# robotWagen_arrduino.net
KiCad netlist of a schematic drawn in EAGLE
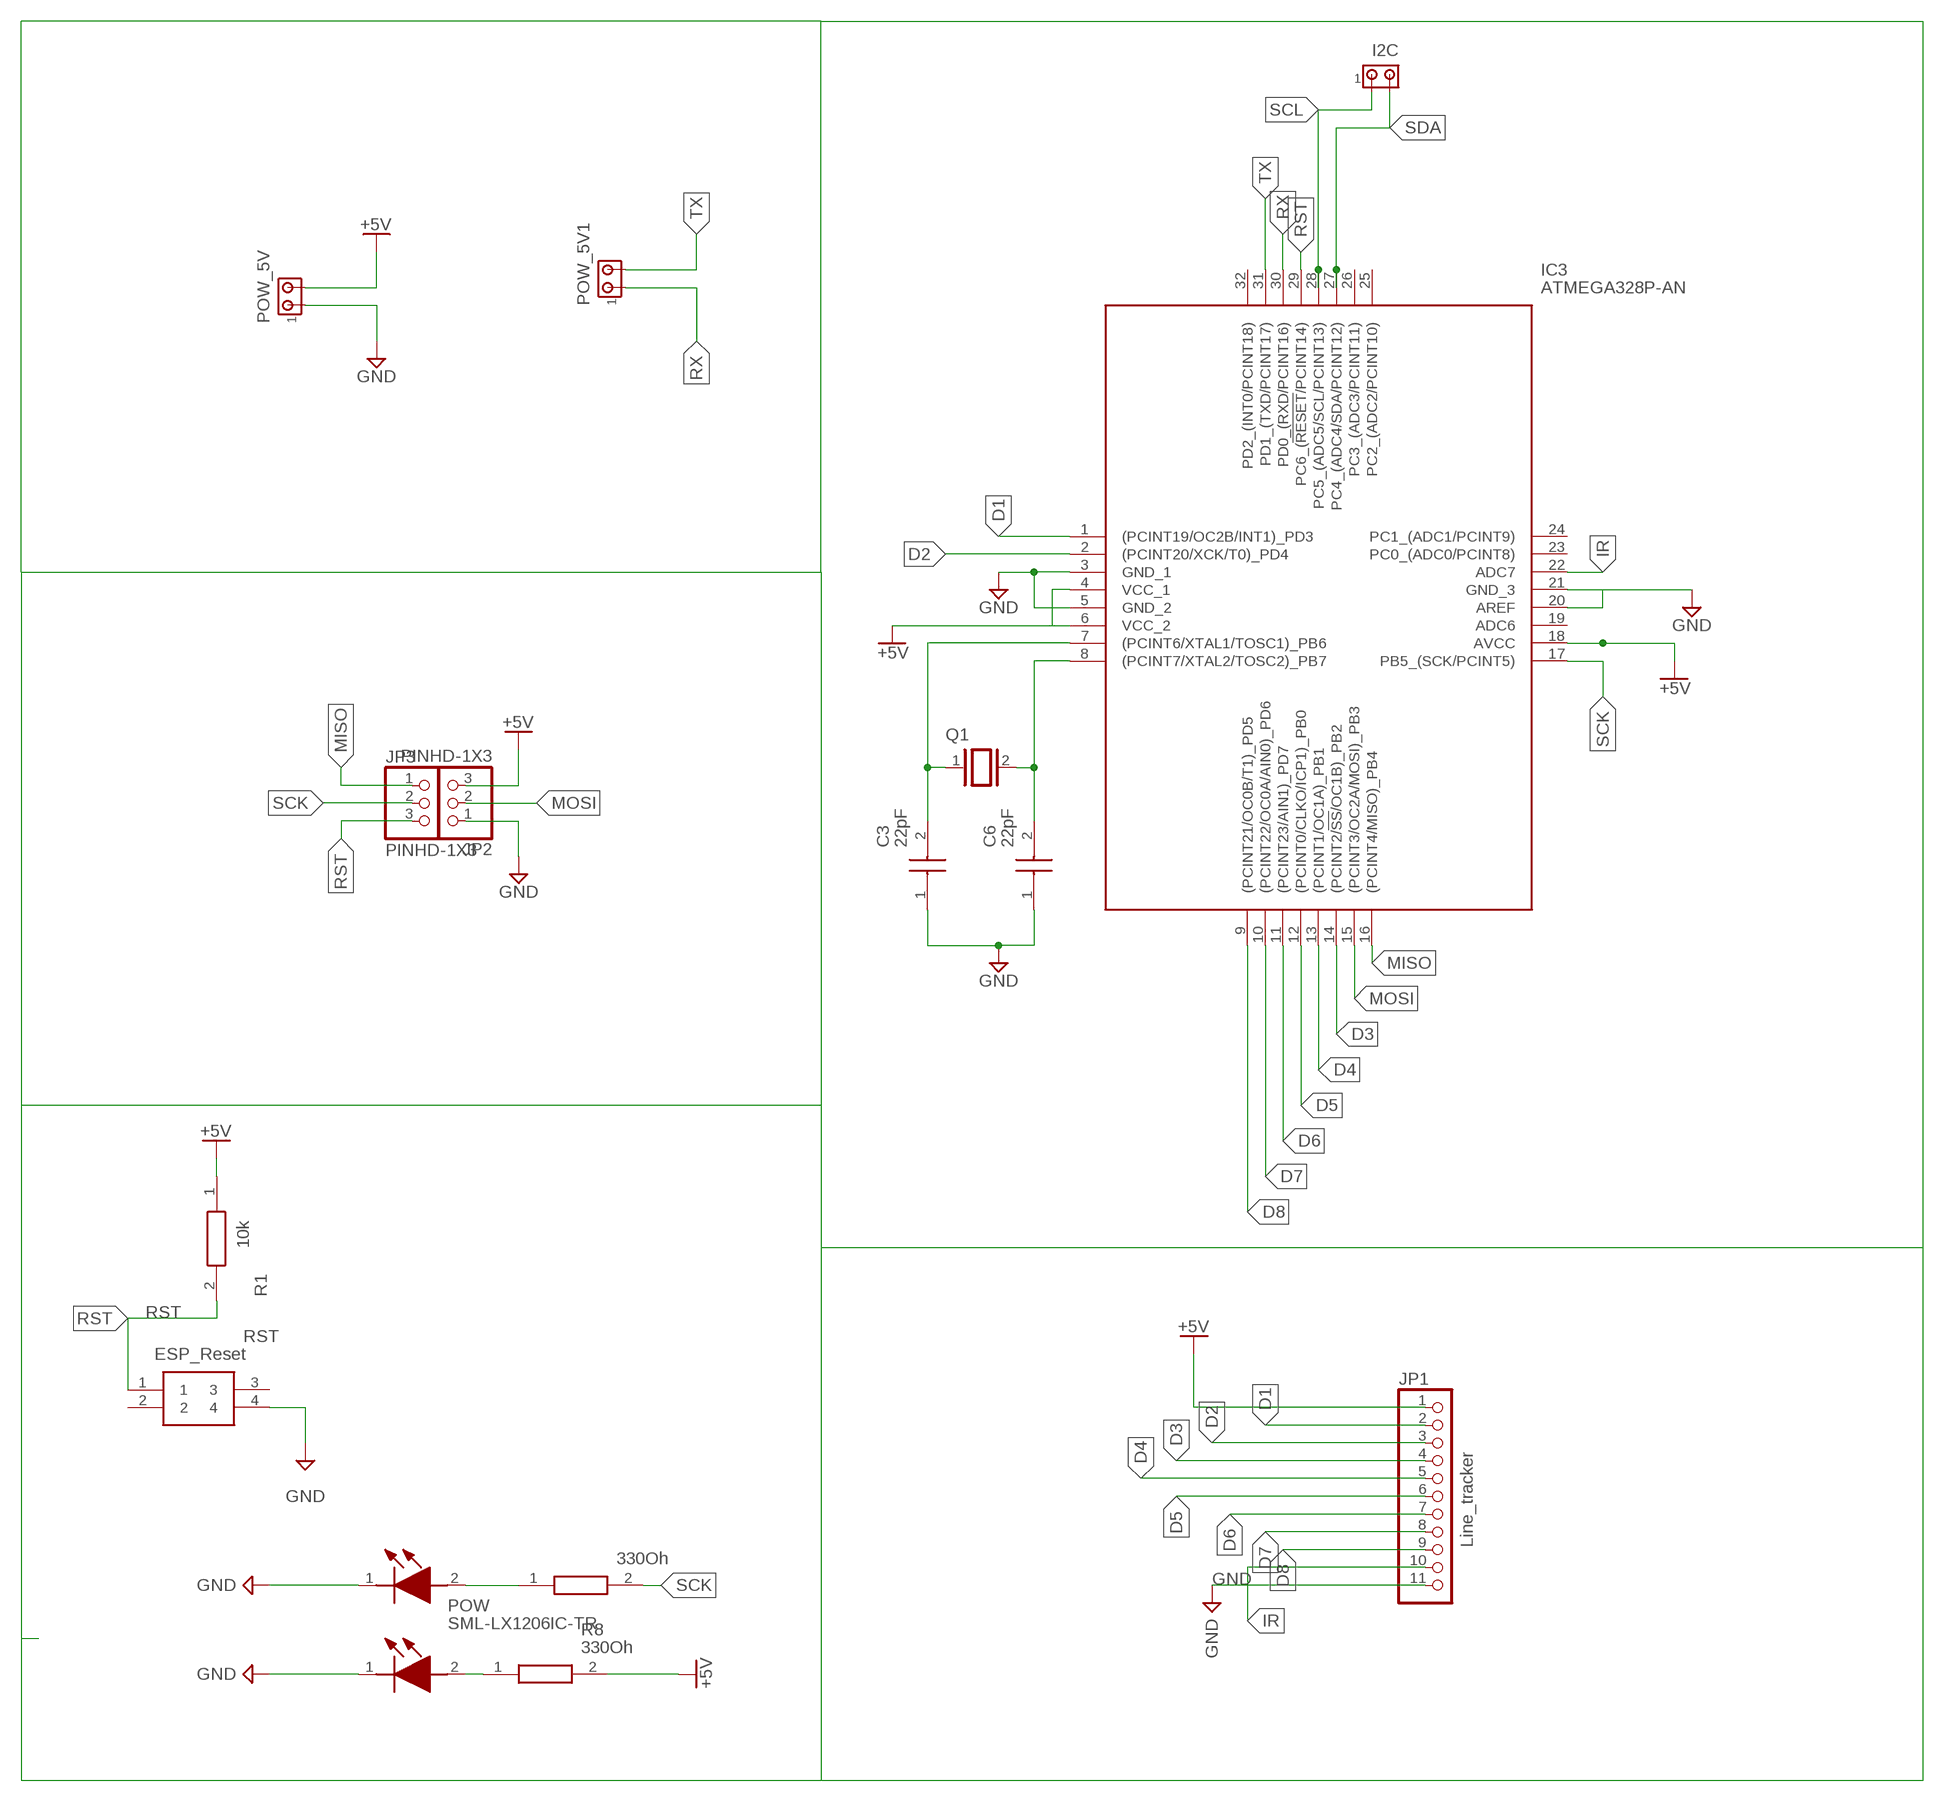
[diagram p0: schematic, sheet 1]

(export (version "E")
  (design (tool "Eeschema 10.0.6"))
  (components
    (comp (ref "C3")
      (value "22pF")
      (footprint "eagle-import:CAPC2012X145N")
      (fields
        (field (name "ARROW_PART_NUMBER") "GRM21BR71H104JA01L")
        (field (name "MOUSER_PART_NUMBER") "81-GRM21BR71H104JA01")
      )
      (libsource (lib "eagle-import") (part "GRM21BR71H104JA01L"))
    )
    (comp (ref "C6")
      (value "22pF")
      (footprint "eagle-import:CAPC2012X145N")
      (fields
        (field (name "ARROW_PART_NUMBER") "GRM21BR71H104JA01L")
        (field (name "MOUSER_PART_NUMBER") "81-GRM21BR71H104JA01")
      )
      (libsource (lib "eagle-import") (part "GRM21BR71H104JA01L"))
    )
    (comp (ref "I2C")
      (value "MTA02-156")
      (footprint "eagle-import:1X2MTA")
      (libsource (lib "eagle-import") (part "MTA02-156"))
    )
    (comp (ref "IC3")
      (value "ATMEGA328P-AN")
      (footprint "eagle-import:QFP80P900X900X120-32N")
      (fields (field (name "MOUSER_PART_NUMBER") "556-ATMEGA328P-AN"))
      (libsource (lib "eagle-import") (part "ATMEGA328P-AN"))
    )
    (comp (ref "JP1")
      (value "Line_tracker")
      (footprint "eagle-import:1X11")
      (libsource (lib "eagle-import") (part "PINHD-1X11"))
    )
    (comp (ref "JP2")
      (value "PINHD-1X3")
      (footprint "eagle-import:1X03")
      (libsource (lib "eagle-import") (part "PINHD-1X3"))
    )
    (comp (ref "JP3")
      (value "PINHD-1X3")
      (footprint "eagle-import:1X03")
      (libsource (lib "eagle-import") (part "PINHD-1X3"))
    )
    (comp (ref "POW")
      (value "SML-LX1206IC-TR")
      (footprint "eagle-import:SMLLX1206ICTR")
      (fields (field (name "MOUSER_PART_NUMBER") "696-SML-LX1206IC"))
      (libsource (lib "eagle-import") (part "SML-LX1206IC-TR"))
    )
    (comp (ref "POW_5V")
      (value "MTA02-156")
      (footprint "eagle-import:1X2MTA")
      (libsource (lib "eagle-import") (part "MTA02-156"))
    )
    (comp (ref "POW_5V1")
      (value "MTA02-156")
      (footprint "eagle-import:1X2MTA")
      (libsource (lib "eagle-import") (part "MTA02-156"))
    )
    (comp (ref "Q1")
      (value "XTAL/S")
      (footprint "eagle-import:QS")
      (libsource (lib "eagle-import") (part "XTAL/S"))
    )
    (comp (ref "R1")
      (value "10k")
      (footprint "eagle-import:RESC2012X65N")
      (fields (field (name "MANUFACTURER_PART_NUMBER") "MCWR08X3301FTL"))
      (libsource (lib "eagle-import") (part "MCWR08X3301FTL"))
    )
    (comp (ref "R7")
      (value "330Oh")
      (footprint "eagle-import:RESC2012X65N")
      (fields (field (name "MANUFACTURER_PART_NUMBER") "MCWR08X3301FTL"))
      (libsource (lib "eagle-import") (part "MCWR08X3301FTL"))
    )
    (comp (ref "R8")
      (value "330Oh")
      (footprint "eagle-import:RESC2012X65N")
      (fields (field (name "MANUFACTURER_PART_NUMBER") "MCWR08X3301FTL"))
      (libsource (lib "eagle-import") (part "MCWR08X3301FTL"))
    )
    (comp (ref "RST")
      (value "ESP_Reset")
      (footprint "eagle-import:430182070816")
      (fields
        (field (name "MANUFACTURER_PART_NUMBER") "430182050816")
        (field (name "MOUSER_PART_NUMBER") "710-430182050816")
      )
      (libsource (lib "eagle-import") (part "430182050816"))
    )
    (comp (ref "TX")
      (value "SML-LX1206IC-TR")
      (footprint "eagle-import:SMLLX1206ICTR")
      (fields (field (name "MOUSER_PART_NUMBER") "696-SML-LX1206IC"))
      (libsource (lib "eagle-import") (part "SML-LX1206IC-TR"))
    )
  )
  (nets
    (net (code "1") (name "+5V") (class "Default")
      (node (ref "IC3") (pin "18") (pinfunction "AVCC_18") (pintype "bidirectional"))
      (node (ref "IC3") (pin "4") (pinfunction "VCC_1_4") (pintype "bidirectional"))
      (node (ref "IC3") (pin "6") (pinfunction "VCC_2_6") (pintype "bidirectional"))
      (node (ref "JP1") (pin "1") (pinfunction "1_1") (pintype "passive"))
      (node (ref "JP2") (pin "3") (pinfunction "3_3") (pintype "passive"))
      (node (ref "POW_5V") (pin "2") (pinfunction "2_2") (pintype "passive"))
      (node (ref "R1") (pin "1") (pinfunction "1_1") (pintype "bidirectional"))
      (node (ref "R8") (pin "2") (pinfunction "2_2") (pintype "bidirectional"))
    )
    (net (code "2") (name "D1") (class "Default")
      (node (ref "IC3") (pin "1") (pinfunction "(PCINT19/OC2B/INT1)_PD3_1") (pintype "bidirectional"))
      (node (ref "JP1") (pin "2") (pinfunction "2_2") (pintype "passive"))
    )
    (net (code "3") (name "D2") (class "Default")
      (node (ref "IC3") (pin "2") (pinfunction "(PCINT20/XCK/T0)_PD4_2") (pintype "bidirectional"))
      (node (ref "JP1") (pin "3") (pinfunction "3_3") (pintype "passive"))
    )
    (net (code "4") (name "D3") (class "Default")
      (node (ref "IC3") (pin "14") (pinfunction "(PCINT2/~{SS}/OC1B)_PB2_14") (pintype "bidirectional"))
      (node (ref "JP1") (pin "4") (pinfunction "4_4") (pintype "passive"))
    )
    (net (code "5") (name "D4") (class "Default")
      (node (ref "IC3") (pin "13") (pinfunction "(PCINT1/OC1A)_PB1_13") (pintype "bidirectional"))
      (node (ref "JP1") (pin "5") (pinfunction "5_5") (pintype "passive"))
    )
    (net (code "6") (name "D5") (class "Default")
      (node (ref "IC3") (pin "12") (pinfunction "(PCINT0/CLKO/ICP1)_PB0_12") (pintype "bidirectional"))
      (node (ref "JP1") (pin "6") (pinfunction "6_6") (pintype "passive"))
    )
    (net (code "7") (name "D6") (class "Default")
      (node (ref "IC3") (pin "11") (pinfunction "(PCINT23/AIN1)_PD7_11") (pintype "bidirectional"))
      (node (ref "JP1") (pin "7") (pinfunction "7_7") (pintype "passive"))
    )
    (net (code "8") (name "D7") (class "Default")
      (node (ref "IC3") (pin "10") (pinfunction "(PCINT22/OC0A/AIN0)_PD6_10") (pintype "bidirectional"))
      (node (ref "JP1") (pin "8") (pinfunction "8_8") (pintype "passive"))
    )
    (net (code "9") (name "D8") (class "Default")
      (node (ref "IC3") (pin "9") (pinfunction "(PCINT21/OC0B/T1)_PD5_9") (pintype "bidirectional"))
      (node (ref "JP1") (pin "9") (pinfunction "9_9") (pintype "passive"))
    )
    (net (code "10") (name "GND") (class "Default")
      (node (ref "C3") (pin "1") (pinfunction "1_1") (pintype "bidirectional"))
      (node (ref "C6") (pin "1") (pinfunction "1_1") (pintype "bidirectional"))
      (node (ref "IC3") (pin "20") (pinfunction "AREF_20") (pintype "bidirectional"))
      (node (ref "IC3") (pin "21") (pinfunction "GND_3_21") (pintype "bidirectional"))
      (node (ref "IC3") (pin "3") (pinfunction "GND_1_3") (pintype "bidirectional"))
      (node (ref "IC3") (pin "5") (pinfunction "GND_2_5") (pintype "bidirectional"))
      (node (ref "JP1") (pin "11") (pinfunction "11_11") (pintype "passive"))
      (node (ref "JP2") (pin "1") (pinfunction "1_1") (pintype "passive"))
      (node (ref "POW") (pin "1") (pinfunction "K_1") (pintype "bidirectional"))
      (node (ref "POW_5V") (pin "1") (pinfunction "1_1") (pintype "passive"))
      (node (ref "RST") (pin "4") (pinfunction "4_4") (pintype "bidirectional"))
      (node (ref "TX") (pin "1") (pinfunction "K_1") (pintype "bidirectional"))
    )
    (net (code "11") (name "IR") (class "Default")
      (node (ref "IC3") (pin "22") (pinfunction "ADC7_22") (pintype "bidirectional"))
      (node (ref "JP1") (pin "10") (pinfunction "10_10") (pintype "passive"))
    )
    (net (code "12") (name "MISO") (class "Default")
      (node (ref "IC3") (pin "16") (pinfunction "(PCINT4/MISO)_PB4_16") (pintype "bidirectional"))
      (node (ref "JP3") (pin "1") (pinfunction "1_1") (pintype "passive"))
    )
    (net (code "13") (name "MOSI") (class "Default")
      (node (ref "IC3") (pin "15") (pinfunction "(PCINT3/OC2A/MOSI)_PB3_15") (pintype "bidirectional"))
      (node (ref "JP2") (pin "2") (pinfunction "2_2") (pintype "passive"))
    )
    (net (code "14") (name "Net-(IC3-(PCINT6{slash}XTAL1{slash}TOSC1)_PB6)") (class "Default")
      (node (ref "C3") (pin "2") (pinfunction "2_2") (pintype "bidirectional"))
      (node (ref "IC3") (pin "7") (pinfunction "(PCINT6/XTAL1/TOSC1)_PB6_7") (pintype "bidirectional"))
      (node (ref "Q1") (pin "1") (pinfunction "1_1") (pintype "passive"))
    )
    (net (code "15") (name "Net-(IC3-(PCINT7{slash}XTAL2{slash}TOSC2)_PB7)") (class "Default")
      (node (ref "C6") (pin "2") (pinfunction "2_2") (pintype "bidirectional"))
      (node (ref "IC3") (pin "8") (pinfunction "(PCINT7/XTAL2/TOSC2)_PB7_8") (pintype "bidirectional"))
      (node (ref "Q1") (pin "2") (pinfunction "2_2") (pintype "passive"))
    )
    (net (code "16") (name "Net-(POW-A)") (class "Default")
      (node (ref "POW") (pin "2") (pinfunction "A_2") (pintype "bidirectional"))
      (node (ref "R8") (pin "1") (pinfunction "1_1") (pintype "bidirectional"))
    )
    (net (code "17") (name "Net-(TX-A)") (class "Default")
      (node (ref "R7") (pin "1") (pinfunction "1_1") (pintype "bidirectional"))
      (node (ref "TX") (pin "2") (pinfunction "A_2") (pintype "bidirectional"))
    )
    (net (code "18") (name "RST") (class "Default")
      (node (ref "IC3") (pin "29") (pinfunction "PC6_(~{RESET}/PCINT14)_29") (pintype "bidirectional"))
      (node (ref "JP3") (pin "3") (pinfunction "3_3") (pintype "passive"))
      (node (ref "R1") (pin "2") (pinfunction "2_2") (pintype "bidirectional"))
      (node (ref "RST") (pin "1") (pinfunction "1_1") (pintype "bidirectional"))
    )
    (net (code "19") (name "RX") (class "Default")
      (node (ref "IC3") (pin "30") (pinfunction "PD0_(RXD/PCINT16)_30") (pintype "bidirectional"))
      (node (ref "POW_5V1") (pin "1") (pinfunction "1_1") (pintype "passive"))
    )
    (net (code "20") (name "SCK") (class "Default")
      (node (ref "IC3") (pin "17") (pinfunction "PB5_(SCK/PCINT5)_17") (pintype "bidirectional"))
      (node (ref "JP3") (pin "2") (pinfunction "2_2") (pintype "passive"))
      (node (ref "R7") (pin "2") (pinfunction "2_2") (pintype "bidirectional"))
    )
    (net (code "21") (name "SCL") (class "Default")
      (node (ref "I2C") (pin "1") (pinfunction "1_1") (pintype "passive"))
      (node (ref "IC3") (pin "28") (pinfunction "PC5_(ADC5/SCL/PCINT13)_28") (pintype "bidirectional"))
    )
    (net (code "22") (name "SDA") (class "Default")
      (node (ref "I2C") (pin "2") (pinfunction "2_2") (pintype "passive"))
      (node (ref "IC3") (pin "27") (pinfunction "PC4_(ADC4/SDA/PCINT12)_27") (pintype "bidirectional"))
    )
    (net (code "23") (name "TX") (class "Default")
      (node (ref "IC3") (pin "31") (pinfunction "PD1_(TXD/PCINT17)_31") (pintype "bidirectional"))
      (node (ref "POW_5V1") (pin "2") (pinfunction "2_2") (pintype "passive"))
    )
    (net (code "24") (name "unconnected-(IC3-ADC6-Pad19)") (class "Default")
      (node (ref "IC3") (pin "19") (pinfunction "ADC6_19") (pintype "bidirectional"))
    )
    (net (code "25") (name "unconnected-(IC3-PC0_(ADC0{slash}PCINT8)-Pad23)") (class "Default")
      (node (ref "IC3") (pin "23") (pinfunction "PC0_(ADC0/PCINT8)_23") (pintype "bidirectional"))
    )
    (net (code "26") (name "unconnected-(IC3-PC1_(ADC1{slash}PCINT9)-Pad24)") (class "Default")
      (node (ref "IC3") (pin "24") (pinfunction "PC1_(ADC1/PCINT9)_24") (pintype "bidirectional"))
    )
    (net (code "27") (name "unconnected-(IC3-PC2_(ADC2{slash}PCINT10)-Pad25)") (class "Default")
      (node (ref "IC3") (pin "25") (pinfunction "PC2_(ADC2/PCINT10)_25") (pintype "bidirectional"))
    )
    (net (code "28") (name "unconnected-(IC3-PC3_(ADC3{slash}PCINT11)-Pad26)") (class "Default")
      (node (ref "IC3") (pin "26") (pinfunction "PC3_(ADC3/PCINT11)_26") (pintype "bidirectional"))
    )
    (net (code "29") (name "unconnected-(IC3-PD2_(INT0{slash}PCINT18)-Pad32)") (class "Default")
      (node (ref "IC3") (pin "32") (pinfunction "PD2_(INT0/PCINT18)_32") (pintype "bidirectional"))
    )
    (net (code "30") (name "unconnected-(RST-Pad2)") (class "Default")
      (node (ref "RST") (pin "2") (pinfunction "2_2") (pintype "bidirectional"))
    )
    (net (code "31") (name "unconnected-(RST-Pad3)") (class "Default")
      (node (ref "RST") (pin "3") (pinfunction "3_3") (pintype "bidirectional"))
    )
  )
)
